# pixel.net
KiCad netlist of a schematic drawn in Altium Designer
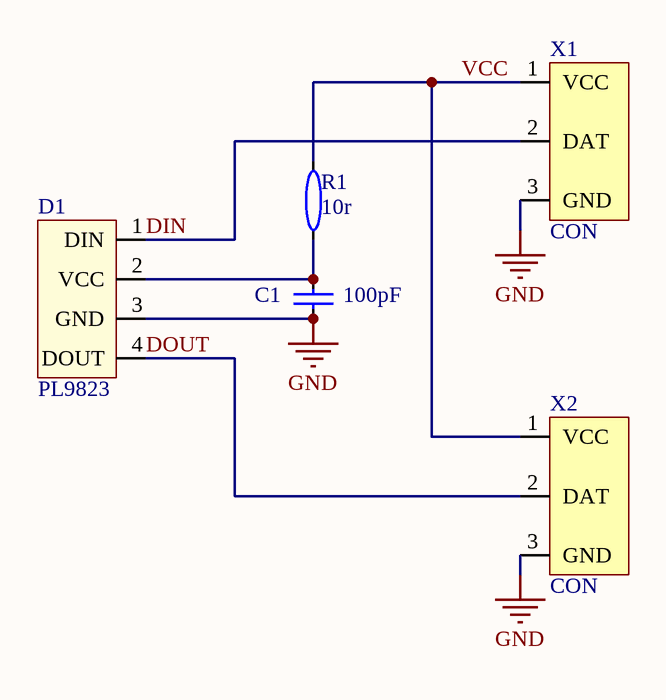
[diagram p0: pixel.SchDoc]

(export (version "E")
  (design (tool "Eeschema 10.0.6"))
  (components
    (comp (ref "C1")
      (value "100pF")
      (footprint "0805 CAP")
      (description "Capacitor")
      (fields (field (name "Comment") "Cap") (field (name "PUBLISHER") "Altium Limited"))
      (libsource (lib "pixel") (part "Cap"))
    )
    (comp (ref "D1") (value "PL9823") (footprint "PL9823 5mm") (libsource (lib "pixel") (part "PL9823")))
    (comp (ref "R1")
      (value "10r")
      (footprint "RESC2012X05L")
      (description "Resistor")
      (fields (field (name "Comment") "Res2") (field (name "PUBLISHER") "Altium Limited"))
      (libsource (lib "pixel") (part "Res2"))
    )
    (comp (ref "X1") (value "CON") (footprint "CON3") (libsource (lib "pixel") (part "CON")))
    (comp (ref "X2") (value "CON") (footprint "CON3") (libsource (lib "pixel") (part "CON")))
  )
  (nets
    (net (code "1") (name "/DIN") (class "Default")
      (node (ref "D1") (pin "1") (pinfunction "DIN_1") (pintype "passive"))
      (node (ref "X1") (pin "2") (pinfunction "DAT_2") (pintype "passive"))
    )
    (net (code "2") (name "/DOUT") (class "Default")
      (node (ref "D1") (pin "4") (pinfunction "DOUT_4") (pintype "passive"))
      (node (ref "X2") (pin "2") (pinfunction "DAT_2") (pintype "passive"))
    )
    (net (code "3") (name "/VCC") (class "Default")
      (node (ref "R1") (pin "2") (pinfunction "2_2") (pintype "passive"))
      (node (ref "X1") (pin "1") (pinfunction "VCC_1") (pintype "passive"))
      (node (ref "X2") (pin "1") (pinfunction "VCC_1") (pintype "passive"))
    )
    (net (code "4") (name "GND") (class "Default")
      (node (ref "C1") (pin "1") (pinfunction "1_1") (pintype "passive"))
      (node (ref "D1") (pin "3") (pinfunction "GND_3") (pintype "passive"))
      (node (ref "X1") (pin "3") (pinfunction "GND_3") (pintype "passive"))
      (node (ref "X2") (pin "3") (pinfunction "GND_3") (pintype "passive"))
    )
    (net (code "5") (name "Net-(D1-VCC)") (class "Default")
      (node (ref "C1") (pin "2") (pinfunction "2_2") (pintype "passive"))
      (node (ref "D1") (pin "2") (pinfunction "VCC_2") (pintype "passive"))
      (node (ref "R1") (pin "1") (pinfunction "1_1") (pintype "passive"))
    )
  )
)
